# protomesure.net
KiCad netlist of a schematic drawn in EAGLE
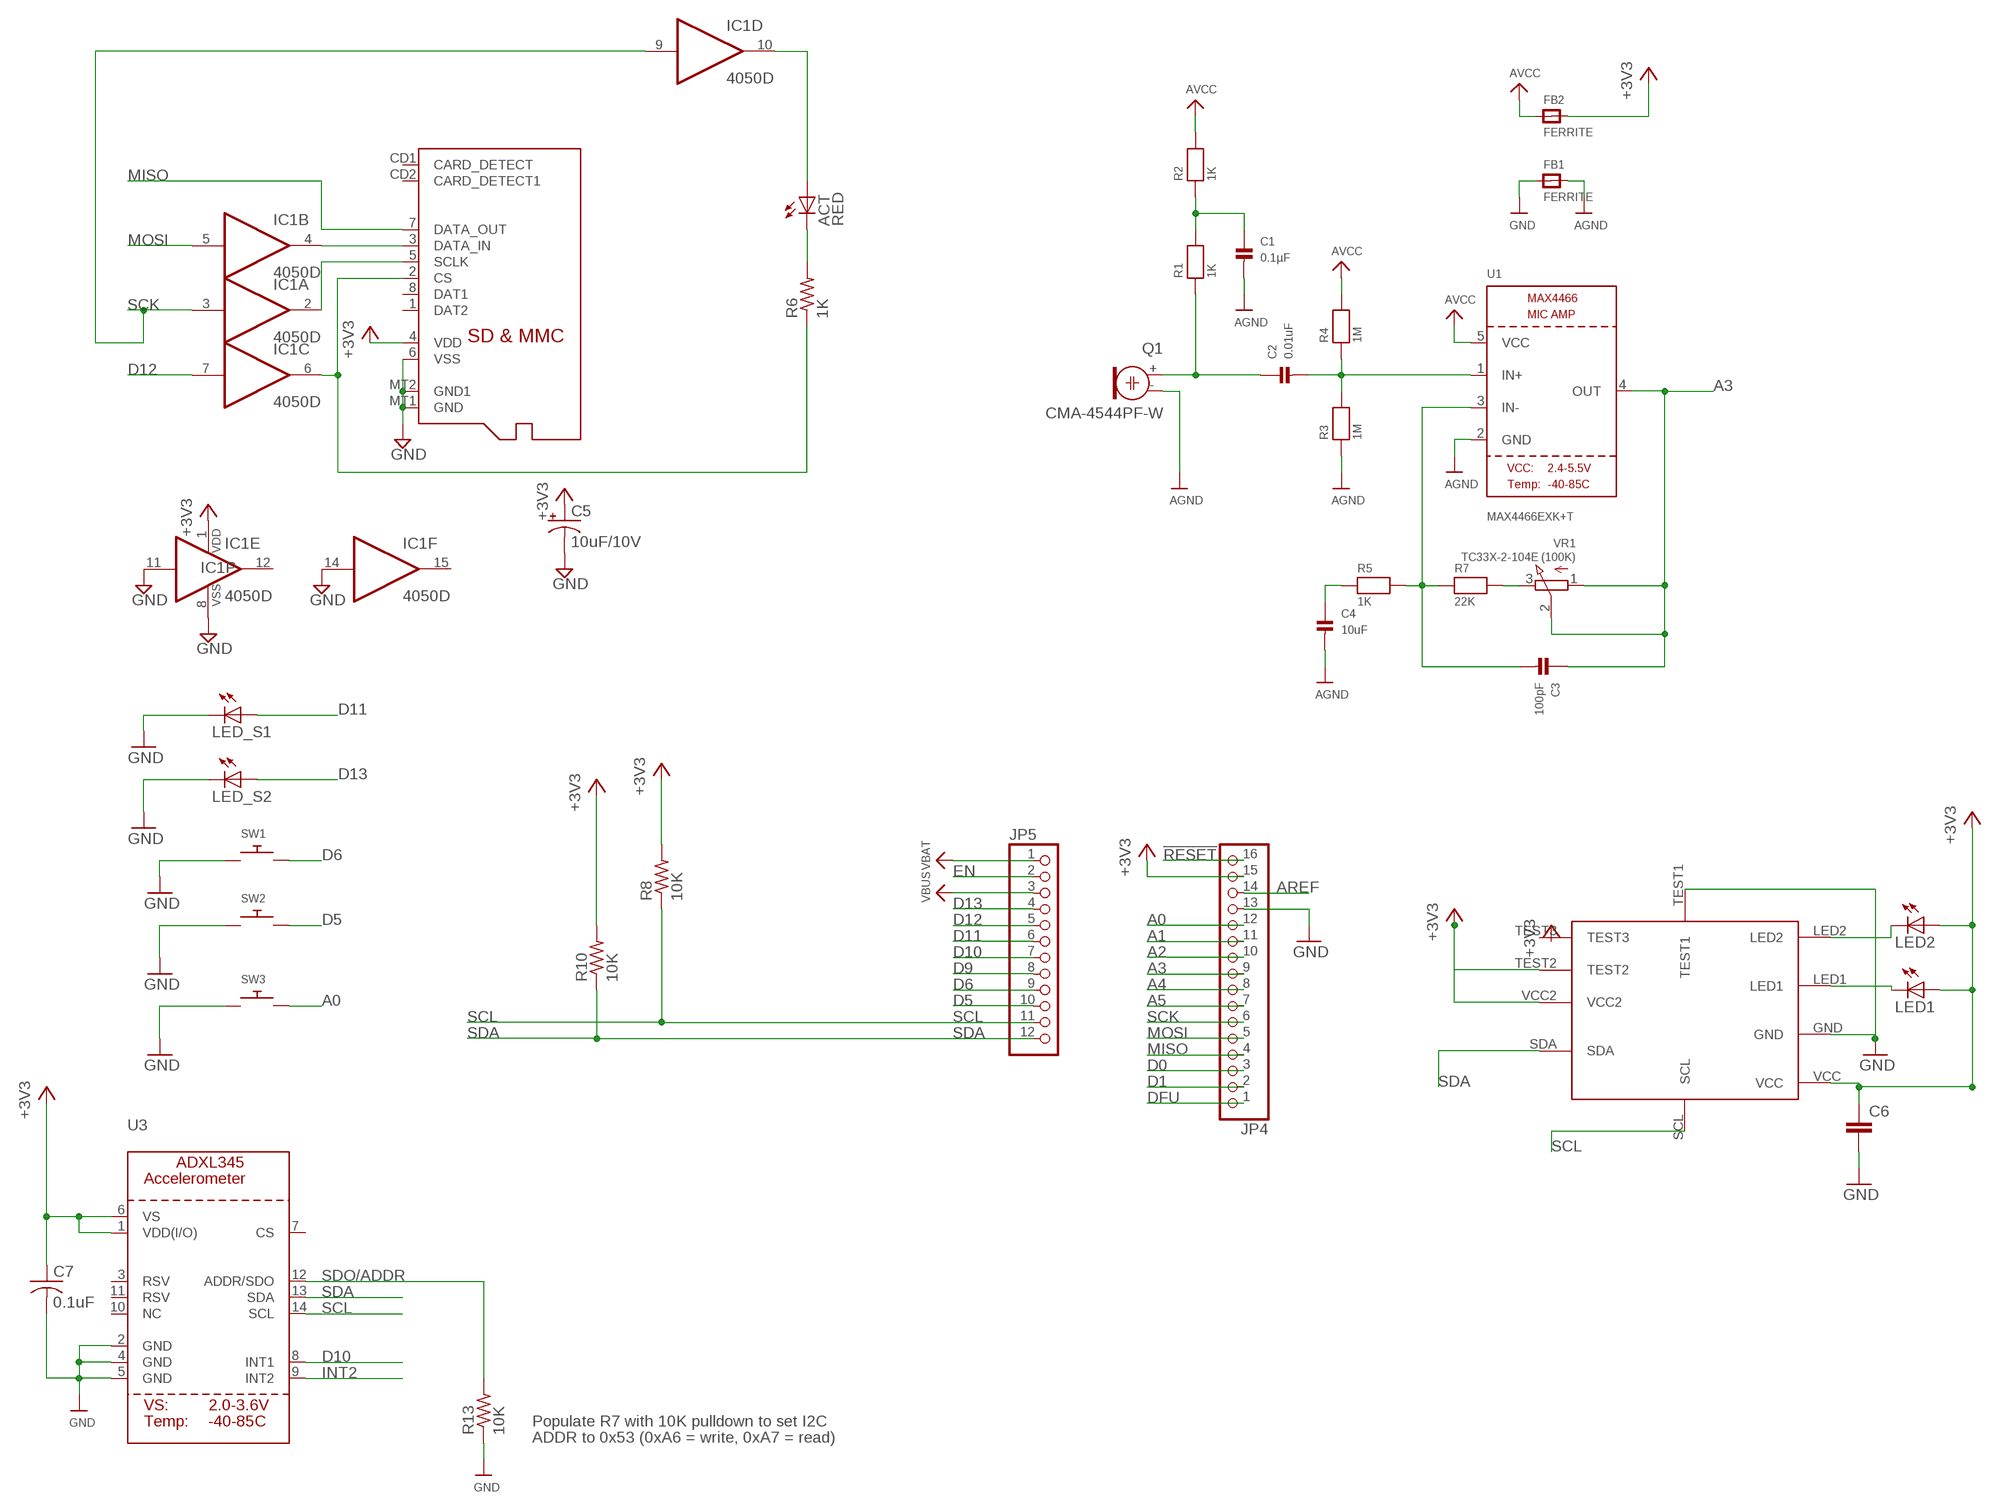
[diagram p0: schematic, sheet 1]

(export (version "E")
  (design (tool "Eeschema 10.0.6"))
  (components
    (comp (ref "ACT")
      (value "RED")
      (footprint "eagle-import:CHIP-LED0805")
      (libsource (lib "eagle-import") (part "LEDCHIP-LED0805"))
    )
    (comp (ref "C1")
      (value "0.1µF")
      (footprint "eagle-import:0805")
      (libsource (lib "eagle-import") (part "CAP_CERAMIC0805"))
    )
    (comp (ref "C2")
      (value "0.01uF")
      (footprint "eagle-import:0805")
      (libsource (lib "eagle-import") (part "CAP_CERAMIC0805"))
    )
    (comp (ref "C3")
      (value "100pF")
      (footprint "eagle-import:0805")
      (libsource (lib "eagle-import") (part "CAP_CERAMIC0805"))
    )
    (comp (ref "C4")
      (value "10uF")
      (footprint "eagle-import:0805")
      (libsource (lib "eagle-import") (part "CAP_CERAMIC0805"))
    )
    (comp (ref "C5")
      (value "10uF/10V")
      (footprint "eagle-import:A_3216-18R")
      (libsource (lib "eagle-import") (part "CPOL-USA/3216-18R"))
    )
    (comp (ref "C6")
      (value "C-EUC0805")
      (footprint "eagle-import:C0805")
      (libsource (lib "eagle-import") (part "C-EUC0805"))
    )
    (comp (ref "C7")
      (value "0.1uF")
      (footprint "eagle-import:C0805")
      (libsource (lib "eagle-import") (part "C-USC0805"))
    )
    (comp (ref "FB1")
      (value "FERRITE")
      (footprint "eagle-import:0805")
      (libsource (lib "eagle-import") (part "FERRITE0805"))
    )
    (comp (ref "FB2")
      (value "FERRITE")
      (footprint "eagle-import:0805")
      (libsource (lib "eagle-import") (part "FERRITE0805"))
    )
    (comp (ref "IC1")
      (value "4050D")
      (footprint "eagle-import:SO16")
      (libsource (lib "eagle-import") (part "4050D"))
    )
    (comp (ref "JP4")
      (value "HEADER-1X16ROUND")
      (footprint "eagle-import:1X16_ROUND")
      (libsource (lib "eagle-import") (part "HEADER-1X16ROUND"))
    )
    (comp (ref "JP5")
      (value "HEADER-1X12")
      (footprint "eagle-import:1X12_ROUND")
      (libsource (lib "eagle-import") (part "HEADER-1X12"))
    )
    (comp (ref "LED1")
      (value "LEDCHIPLED_0805")
      (footprint "eagle-import:CHIPLED_0805")
      (libsource (lib "eagle-import") (part "LEDCHIPLED_0805"))
    )
    (comp (ref "LED2")
      (value "LEDCHIPLED_0805")
      (footprint "eagle-import:CHIPLED_0805")
      (libsource (lib "eagle-import") (part "LEDCHIPLED_0805"))
    )
    (comp (ref "LED_S1")
      (value "LEDCHIPLED_0805")
      (footprint "eagle-import:CHIPLED_0805")
      (libsource (lib "eagle-import") (part "LEDCHIPLED_0805"))
    )
    (comp (ref "LED_S2")
      (value "LEDCHIPLED_0805")
      (footprint "eagle-import:CHIPLED_0805")
      (libsource (lib "eagle-import") (part "LEDCHIPLED_0805"))
    )
    (comp (ref "Q1")
      (value "CMA-4544PF-W")
      (footprint "eagle-import:ELECTRET_9.7")
      (libsource (lib "eagle-import") (part "ELECTRET"))
    )
    (comp (ref "R1")
      (value "1K")
      (footprint "eagle-import:0805")
      (libsource (lib "eagle-import") (part "RESISTOR0805"))
    )
    (comp (ref "R2")
      (value "1K")
      (footprint "eagle-import:0805")
      (libsource (lib "eagle-import") (part "RESISTOR0805"))
    )
    (comp (ref "R3")
      (value "1M")
      (footprint "eagle-import:0805")
      (libsource (lib "eagle-import") (part "RESISTOR0805"))
    )
    (comp (ref "R4")
      (value "1M")
      (footprint "eagle-import:0805")
      (libsource (lib "eagle-import") (part "RESISTOR0805"))
    )
    (comp (ref "R5")
      (value "1K")
      (footprint "eagle-import:0805")
      (libsource (lib "eagle-import") (part "RESISTOR0805"))
    )
    (comp (ref "R6")
      (value "1K")
      (footprint "eagle-import:R0805")
      (libsource (lib "eagle-import") (part "R-US_R0805"))
    )
    (comp (ref "R7")
      (value "22K")
      (footprint "eagle-import:0805")
      (libsource (lib "eagle-import") (part "RESISTOR0805"))
    )
    (comp (ref "R8")
      (value "10K")
      (footprint "eagle-import:R0805")
      (libsource (lib "eagle-import") (part "R-US_R0805"))
    )
    (comp (ref "R10")
      (value "10K")
      (footprint "eagle-import:R0805")
      (libsource (lib "eagle-import") (part "R-US_R0805"))
    )
    (comp (ref "R13")
      (value "10K")
      (footprint "eagle-import:R0805")
      (libsource (lib "eagle-import") (part "R-US_R0805"))
    )
    (comp (ref "SW1")
      (value "SWITCH_PUSHBUTTONEVQ-PE")
      (footprint "eagle-import:TACT_PANA-EVQ")
      (libsource (lib "eagle-import") (part "SWITCH_PUSHBUTTONEVQ-PE"))
    )
    (comp (ref "SW2")
      (value "SWITCH_PUSHBUTTONEVQ-PE")
      (footprint "eagle-import:TACT_PANA-EVQ")
      (libsource (lib "eagle-import") (part "SWITCH_PUSHBUTTONEVQ-PE"))
    )
    (comp (ref "SW3")
      (value "SWITCH_PUSHBUTTONEVQ-PE")
      (footprint "eagle-import:TACT_PANA-EVQ")
      (libsource (lib "eagle-import") (part "SWITCH_PUSHBUTTONEVQ-PE"))
    )
    (comp (ref "U$31")
      (value "BH1790")
      (footprint "eagle-import:BH1790")
      (libsource (lib "eagle-import") (part "BH1790"))
    )
    (comp (ref "U1")
      (value "MAX4466EXK+T")
      (footprint "eagle-import:SC70-5")
      (libsource (lib "eagle-import") (part "MAX4466{dblquote}{dblquote}"))
    )
    (comp (ref "U3")
      (value "ACCEL_ADXL345")
      (footprint "eagle-import:LGA14")
      (libsource (lib "eagle-import") (part "ACCEL_ADXL345"))
    )
    (comp (ref "VR1")
      (value "TC33X-2-104E (100K)")
      (footprint "eagle-import:TRIMPOT_BOURNS_TC33X-2")
      (libsource (lib "eagle-import") (part "TRIMPOTTC33X-2"))
    )
    (comp (ref "X1")
      (value "MICROSD")
      (footprint "eagle-import:MICROSD")
      (libsource (lib "eagle-import") (part "MICROSD"))
    )
  )
  (nets
    (net (code "1") (name "+3V3") (class "Default")
      (node (ref "C5") (pin "+") (pinfunction "+_+") (pintype "passive"))
      (node (ref "C6") (pin "1") (pinfunction "1_1") (pintype "passive"))
      (node (ref "C7") (pin "1") (pinfunction "1_1") (pintype "passive"))
      (node (ref "FB2") (pin "2") (pinfunction "P$2_2") (pintype "passive"))
      (node (ref "IC1") (pin "1") (pinfunction "VDD_1") (pintype "power_in"))
      (node (ref "JP4") (pin "15") (pinfunction "15_15") (pintype "passive"))
      (node (ref "LED1") (pin "A") (pinfunction "A_A") (pintype "passive"))
      (node (ref "LED2") (pin "A") (pinfunction "A_A") (pintype "passive"))
      (node (ref "R10") (pin "2") (pinfunction "2_2") (pintype "passive"))
      (node (ref "R8") (pin "2") (pinfunction "2_2") (pintype "passive"))
      (node (ref "U$31") (pin "TEST2") (pinfunction "TEST2_TEST2") (pintype "bidirectional"))
      (node (ref "U$31") (pin "VCC") (pinfunction "VCC_VCC") (pintype "bidirectional"))
      (node (ref "U$31") (pin "VCC2") (pinfunction "VCC2_VCC2") (pintype "bidirectional"))
      (node (ref "U3") (pin "1") (pinfunction "VDD(I/O)_1") (pintype "bidirectional"))
      (node (ref "U3") (pin "6") (pinfunction "VS_6") (pintype "bidirectional"))
      (node (ref "X1") (pin "4") (pinfunction "VDD_4") (pintype "power_in"))
    )
    (net (code "2") (name "/A0") (class "Default")
      (node (ref "JP4") (pin "12") (pinfunction "12_12") (pintype "passive"))
      (node (ref "SW3") (pin "P$2") (pinfunction "P$2_P$2") (pintype "passive"))
    )
    (net (code "3") (name "/A1") (class "Default")
      (node (ref "JP4") (pin "11") (pinfunction "11_11") (pintype "passive"))
    )
    (net (code "4") (name "/A2") (class "Default")
      (node (ref "JP4") (pin "10") (pinfunction "10_10") (pintype "passive"))
    )
    (net (code "5") (name "/A3") (class "Default")
      (node (ref "C3") (pin "1") (pinfunction "P$1_1") (pintype "passive"))
      (node (ref "JP4") (pin "9") (pinfunction "9_9") (pintype "passive"))
      (node (ref "U1") (pin "4") (pinfunction "OUT_4") (pintype "bidirectional"))
      (node (ref "VR1") (pin "1") (pinfunction "A_1") (pintype "passive"))
      (node (ref "VR1") (pin "2") (pinfunction "S_2") (pintype "passive"))
    )
    (net (code "6") (name "/A4") (class "Default")
      (node (ref "JP4") (pin "8") (pinfunction "8_8") (pintype "passive"))
    )
    (net (code "7") (name "/A5") (class "Default")
      (node (ref "JP4") (pin "7") (pinfunction "7_7") (pintype "passive"))
    )
    (net (code "8") (name "/AREF") (class "Default")
      (node (ref "JP4") (pin "14") (pinfunction "14_14") (pintype "passive"))
    )
    (net (code "9") (name "/D0") (class "Default")
      (node (ref "JP4") (pin "3") (pinfunction "3_3") (pintype "passive"))
    )
    (net (code "10") (name "/D1") (class "Default")
      (node (ref "JP4") (pin "2") (pinfunction "2_2") (pintype "passive"))
    )
    (net (code "11") (name "/D5") (class "Default")
      (node (ref "JP5") (pin "10") (pinfunction "10_10") (pintype "passive"))
      (node (ref "SW2") (pin "P$2") (pinfunction "P$2_P$2") (pintype "passive"))
    )
    (net (code "12") (name "/D6") (class "Default")
      (node (ref "JP5") (pin "9") (pinfunction "9_9") (pintype "passive"))
      (node (ref "SW1") (pin "P$2") (pinfunction "P$2_P$2") (pintype "passive"))
    )
    (net (code "13") (name "/D9") (class "Default")
      (node (ref "JP5") (pin "8") (pinfunction "8_8") (pintype "passive"))
    )
    (net (code "14") (name "/D10") (class "Default")
      (node (ref "JP5") (pin "7") (pinfunction "7_7") (pintype "passive"))
      (node (ref "U3") (pin "8") (pinfunction "INT1_8") (pintype "bidirectional"))
    )
    (net (code "15") (name "/D11") (class "Default")
      (node (ref "JP5") (pin "6") (pinfunction "6_6") (pintype "passive"))
      (node (ref "LED_S1") (pin "A") (pinfunction "A_A") (pintype "passive"))
    )
    (net (code "16") (name "/D12") (class "Default")
      (node (ref "IC1") (pin "7") (pinfunction "I_7") (pintype "input"))
      (node (ref "JP5") (pin "5") (pinfunction "5_5") (pintype "passive"))
    )
    (net (code "17") (name "/D13") (class "Default")
      (node (ref "JP5") (pin "4") (pinfunction "4_4") (pintype "passive"))
      (node (ref "LED_S2") (pin "A") (pinfunction "A_A") (pintype "passive"))
    )
    (net (code "18") (name "/DFU") (class "Default")
      (node (ref "JP4") (pin "1") (pinfunction "1_1") (pintype "passive"))
    )
    (net (code "19") (name "/EN") (class "Default")
      (node (ref "JP5") (pin "2") (pinfunction "2_2") (pintype "passive"))
    )
    (net (code "20") (name "/INT2") (class "Default")
      (node (ref "U3") (pin "9") (pinfunction "INT2_9") (pintype "bidirectional"))
    )
    (net (code "21") (name "/MISO") (class "Default")
      (node (ref "JP4") (pin "4") (pinfunction "4_4") (pintype "passive"))
      (node (ref "X1") (pin "7") (pinfunction "DATA_OUT_7") (pintype "output"))
    )
    (net (code "22") (name "/MOSI") (class "Default")
      (node (ref "IC1") (pin "5") (pinfunction "I_5") (pintype "input"))
      (node (ref "JP4") (pin "5") (pinfunction "5_5") (pintype "passive"))
    )
    (net (code "23") (name "/SCK") (class "Default")
      (node (ref "IC1") (pin "3") (pinfunction "I_3") (pintype "input"))
      (node (ref "IC1") (pin "9") (pinfunction "I_9") (pintype "input"))
      (node (ref "JP4") (pin "6") (pinfunction "6_6") (pintype "passive"))
    )
    (net (code "24") (name "/SCL") (class "Default")
      (node (ref "JP5") (pin "11") (pinfunction "11_11") (pintype "passive"))
      (node (ref "R8") (pin "1") (pinfunction "1_1") (pintype "passive"))
      (node (ref "U$31") (pin "SCL") (pinfunction "SCL_SCL") (pintype "bidirectional"))
      (node (ref "U3") (pin "14") (pinfunction "SCL_14") (pintype "bidirectional"))
    )
    (net (code "25") (name "/SDA") (class "Default")
      (node (ref "JP5") (pin "12") (pinfunction "12_12") (pintype "passive"))
      (node (ref "R10") (pin "1") (pinfunction "1_1") (pintype "passive"))
      (node (ref "U$31") (pin "SDA") (pinfunction "SDA_SDA") (pintype "bidirectional"))
      (node (ref "U3") (pin "13") (pinfunction "SDA_13") (pintype "bidirectional"))
    )
    (net (code "26") (name "/SDO{slash}ADDR") (class "Default")
      (node (ref "R13") (pin "2") (pinfunction "2_2") (pintype "passive"))
      (node (ref "U3") (pin "12") (pinfunction "ADDR/SDO_12") (pintype "bidirectional"))
    )
    (net (code "27") (name "/~{RESET}") (class "Default")
      (node (ref "JP4") (pin "16") (pinfunction "16_16") (pintype "passive"))
    )
    (net (code "28") (name "AGND") (class "Default")
      (node (ref "C1") (pin "2") (pinfunction "P$2_2") (pintype "passive"))
      (node (ref "C4") (pin "2") (pinfunction "P$2_2") (pintype "passive"))
      (node (ref "FB1") (pin "2") (pinfunction "P$2_2") (pintype "passive"))
      (node (ref "Q1") (pin "-") (pinfunction "1_-") (pintype "passive"))
      (node (ref "R3") (pin "1") (pinfunction "1_1") (pintype "passive"))
      (node (ref "U1") (pin "2") (pinfunction "GND_2") (pintype "bidirectional"))
    )
    (net (code "29") (name "AVCC") (class "Default")
      (node (ref "FB2") (pin "1") (pinfunction "P$1_1") (pintype "passive"))
      (node (ref "R2") (pin "2") (pinfunction "2_2") (pintype "passive"))
      (node (ref "R4") (pin "2") (pinfunction "2_2") (pintype "passive"))
      (node (ref "U1") (pin "5") (pinfunction "VCC_5") (pintype "bidirectional"))
    )
    (net (code "30") (name "GND") (class "Default")
      (node (ref "C5") (pin "-") (pinfunction "-_-") (pintype "passive"))
      (node (ref "C6") (pin "2") (pinfunction "2_2") (pintype "passive"))
      (node (ref "C7") (pin "2") (pinfunction "2_2") (pintype "passive"))
      (node (ref "FB1") (pin "1") (pinfunction "P$1_1") (pintype "passive"))
      (node (ref "IC1") (pin "11") (pinfunction "I_11") (pintype "input"))
      (node (ref "IC1") (pin "14") (pinfunction "I_14") (pintype "input"))
      (node (ref "IC1") (pin "8") (pinfunction "VSS_8") (pintype "power_in"))
      (node (ref "JP4") (pin "13") (pinfunction "13_13") (pintype "passive"))
      (node (ref "LED_S1") (pin "C") (pinfunction "C_C") (pintype "passive"))
      (node (ref "LED_S2") (pin "C") (pinfunction "C_C") (pintype "passive"))
      (node (ref "R13") (pin "1") (pinfunction "1_1") (pintype "passive"))
      (node (ref "SW1") (pin "P$1") (pinfunction "P$1_P$1") (pintype "passive"))
      (node (ref "SW2") (pin "P$1") (pinfunction "P$1_P$1") (pintype "passive"))
      (node (ref "SW3") (pin "P$1") (pinfunction "P$1_P$1") (pintype "passive"))
      (node (ref "U$31") (pin "GND") (pinfunction "GND_GND") (pintype "bidirectional"))
      (node (ref "U$31") (pin "TEST1") (pinfunction "TEST1_TEST1") (pintype "bidirectional"))
      (node (ref "U3") (pin "2") (pinfunction "GND_2") (pintype "bidirectional"))
      (node (ref "U3") (pin "4") (pinfunction "GND_4") (pintype "bidirectional"))
      (node (ref "U3") (pin "5") (pinfunction "GND_5") (pintype "bidirectional"))
      (node (ref "X1") (pin "6") (pinfunction "VSS_6") (pintype "power_in"))
      (node (ref "X1") (pin "MT1") (pinfunction "GND_MT1") (pintype "power_in"))
      (node (ref "X1") (pin "MT2") (pinfunction "GND1_MT2") (pintype "power_in"))
    )
    (net (code "31") (name "Net-(ACT-PadC)") (class "Default")
      (node (ref "ACT") (pin "C") (pinfunction "C_C") (pintype "passive"))
      (node (ref "R6") (pin "2") (pinfunction "2_2") (pintype "passive"))
    )
    (net (code "32") (name "Net-(C1-P$1)") (class "Default")
      (node (ref "C1") (pin "1") (pinfunction "P$1_1") (pintype "passive"))
      (node (ref "R1") (pin "2") (pinfunction "2_2") (pintype "passive"))
      (node (ref "R2") (pin "1") (pinfunction "1_1") (pintype "passive"))
    )
    (net (code "33") (name "Net-(C2-P$1)") (class "Default")
      (node (ref "C2") (pin "1") (pinfunction "P$1_1") (pintype "passive"))
      (node (ref "Q1") (pin "+") (pinfunction "2_+") (pintype "passive"))
      (node (ref "R1") (pin "1") (pinfunction "1_1") (pintype "passive"))
    )
    (net (code "34") (name "Net-(C2-P$2)") (class "Default")
      (node (ref "C2") (pin "2") (pinfunction "P$2_2") (pintype "passive"))
      (node (ref "R3") (pin "2") (pinfunction "2_2") (pintype "passive"))
      (node (ref "R4") (pin "1") (pinfunction "1_1") (pintype "passive"))
      (node (ref "U1") (pin "1") (pinfunction "IN+_1") (pintype "bidirectional"))
    )
    (net (code "35") (name "Net-(C3-P$2)") (class "Default")
      (node (ref "C3") (pin "2") (pinfunction "P$2_2") (pintype "passive"))
      (node (ref "R5") (pin "2") (pinfunction "2_2") (pintype "passive"))
      (node (ref "R7") (pin "1") (pinfunction "1_1") (pintype "passive"))
      (node (ref "U1") (pin "3") (pinfunction "IN-_3") (pintype "bidirectional"))
    )
    (net (code "36") (name "Net-(C4-P$1)") (class "Default")
      (node (ref "C4") (pin "1") (pinfunction "P$1_1") (pintype "passive"))
      (node (ref "R5") (pin "1") (pinfunction "1_1") (pintype "passive"))
    )
    (net (code "37") (name "Net-(IC1A-O)") (class "Default")
      (node (ref "IC1") (pin "2") (pinfunction "O_2") (pintype "output"))
      (node (ref "X1") (pin "5") (pinfunction "SCLK_5") (pintype "input"))
    )
    (net (code "38") (name "Net-(IC1B-O)") (class "Default")
      (node (ref "IC1") (pin "4") (pinfunction "O_4") (pintype "output"))
      (node (ref "X1") (pin "3") (pinfunction "DATA_IN_3") (pintype "input"))
    )
    (net (code "39") (name "Net-(IC1C-O)") (class "Default")
      (node (ref "IC1") (pin "6") (pinfunction "O_6") (pintype "output"))
      (node (ref "R6") (pin "1") (pinfunction "1_1") (pintype "passive"))
      (node (ref "X1") (pin "2") (pinfunction "CS_2") (pintype "input"))
    )
    (net (code "40") (name "Net-(IC1D-O)") (class "Default")
      (node (ref "ACT") (pin "A") (pinfunction "A_A") (pintype "passive"))
      (node (ref "IC1") (pin "10") (pinfunction "O_10") (pintype "output"))
    )
    (net (code "41") (name "Net-(LED1-PadC)") (class "Default")
      (node (ref "LED1") (pin "C") (pinfunction "C_C") (pintype "passive"))
      (node (ref "U$31") (pin "LED1") (pinfunction "LED1_LED1") (pintype "bidirectional"))
    )
    (net (code "42") (name "Net-(LED2-PadC)") (class "Default")
      (node (ref "LED2") (pin "C") (pinfunction "C_C") (pintype "passive"))
      (node (ref "U$31") (pin "LED2") (pinfunction "LED2_LED2") (pintype "bidirectional"))
    )
    (net (code "43") (name "Net-(VR1-E)") (class "Default")
      (node (ref "R7") (pin "2") (pinfunction "2_2") (pintype "passive"))
      (node (ref "VR1") (pin "3") (pinfunction "E_3") (pintype "passive"))
    )
    (net (code "44") (name "VBAT") (class "Default")
      (node (ref "JP5") (pin "1") (pinfunction "1_1") (pintype "passive"))
    )
    (net (code "45") (name "VBUS") (class "Default")
      (node (ref "JP5") (pin "3") (pinfunction "3_3") (pintype "passive"))
    )
    (net (code "46") (name "unconnected-(IC1E-O-Pad12)") (class "Default")
      (node (ref "IC1") (pin "12") (pinfunction "O_12") (pintype "output"))
    )
    (net (code "47") (name "unconnected-(IC1F-O-Pad15)") (class "Default")
      (node (ref "IC1") (pin "15") (pinfunction "O_15") (pintype "output"))
    )
    (net (code "48") (name "unconnected-(U$31-PadTEST3)") (class "Default")
      (node (ref "U$31") (pin "TEST3") (pinfunction "TEST3_TEST3") (pintype "bidirectional"))
    )
    (net (code "49") (name "unconnected-(U3-CS-Pad7)") (class "Default")
      (node (ref "U3") (pin "7") (pinfunction "CS_7") (pintype "bidirectional"))
    )
    (net (code "50") (name "unconnected-(U3-NC-Pad10)") (class "Default")
      (node (ref "U3") (pin "10") (pinfunction "NC_10") (pintype "bidirectional"))
    )
    (net (code "51") (name "unconnected-(U3-RSV-Pad3)") (class "Default")
      (node (ref "U3") (pin "3") (pinfunction "RSV_3") (pintype "bidirectional"))
    )
    (net (code "52") (name "unconnected-(U3-RSV-Pad11)") (class "Default")
      (node (ref "U3") (pin "11") (pinfunction "RSV_11") (pintype "bidirectional"))
    )
    (net (code "53") (name "unconnected-(X1-CARD_DETECT-PadCD1)") (class "Default")
      (node (ref "X1") (pin "CD1") (pinfunction "CARD_DETECT_CD1") (pintype "passive"))
    )
    (net (code "54") (name "unconnected-(X1-CARD_DETECT1-PadCD2)") (class "Default")
      (node (ref "X1") (pin "CD2") (pinfunction "CARD_DETECT1_CD2") (pintype "passive"))
    )
    (net (code "55") (name "unconnected-(X1-DAT1-Pad8)") (class "Default")
      (node (ref "X1") (pin "8") (pinfunction "DAT1_8") (pintype "bidirectional"))
    )
    (net (code "56") (name "unconnected-(X1-DAT2-Pad1)") (class "Default")
      (node (ref "X1") (pin "1") (pinfunction "DAT2_1") (pintype "bidirectional"))
    )
  )
)
